# modem_tda.net
KiCad netlist of a schematic drawn in EAGLE
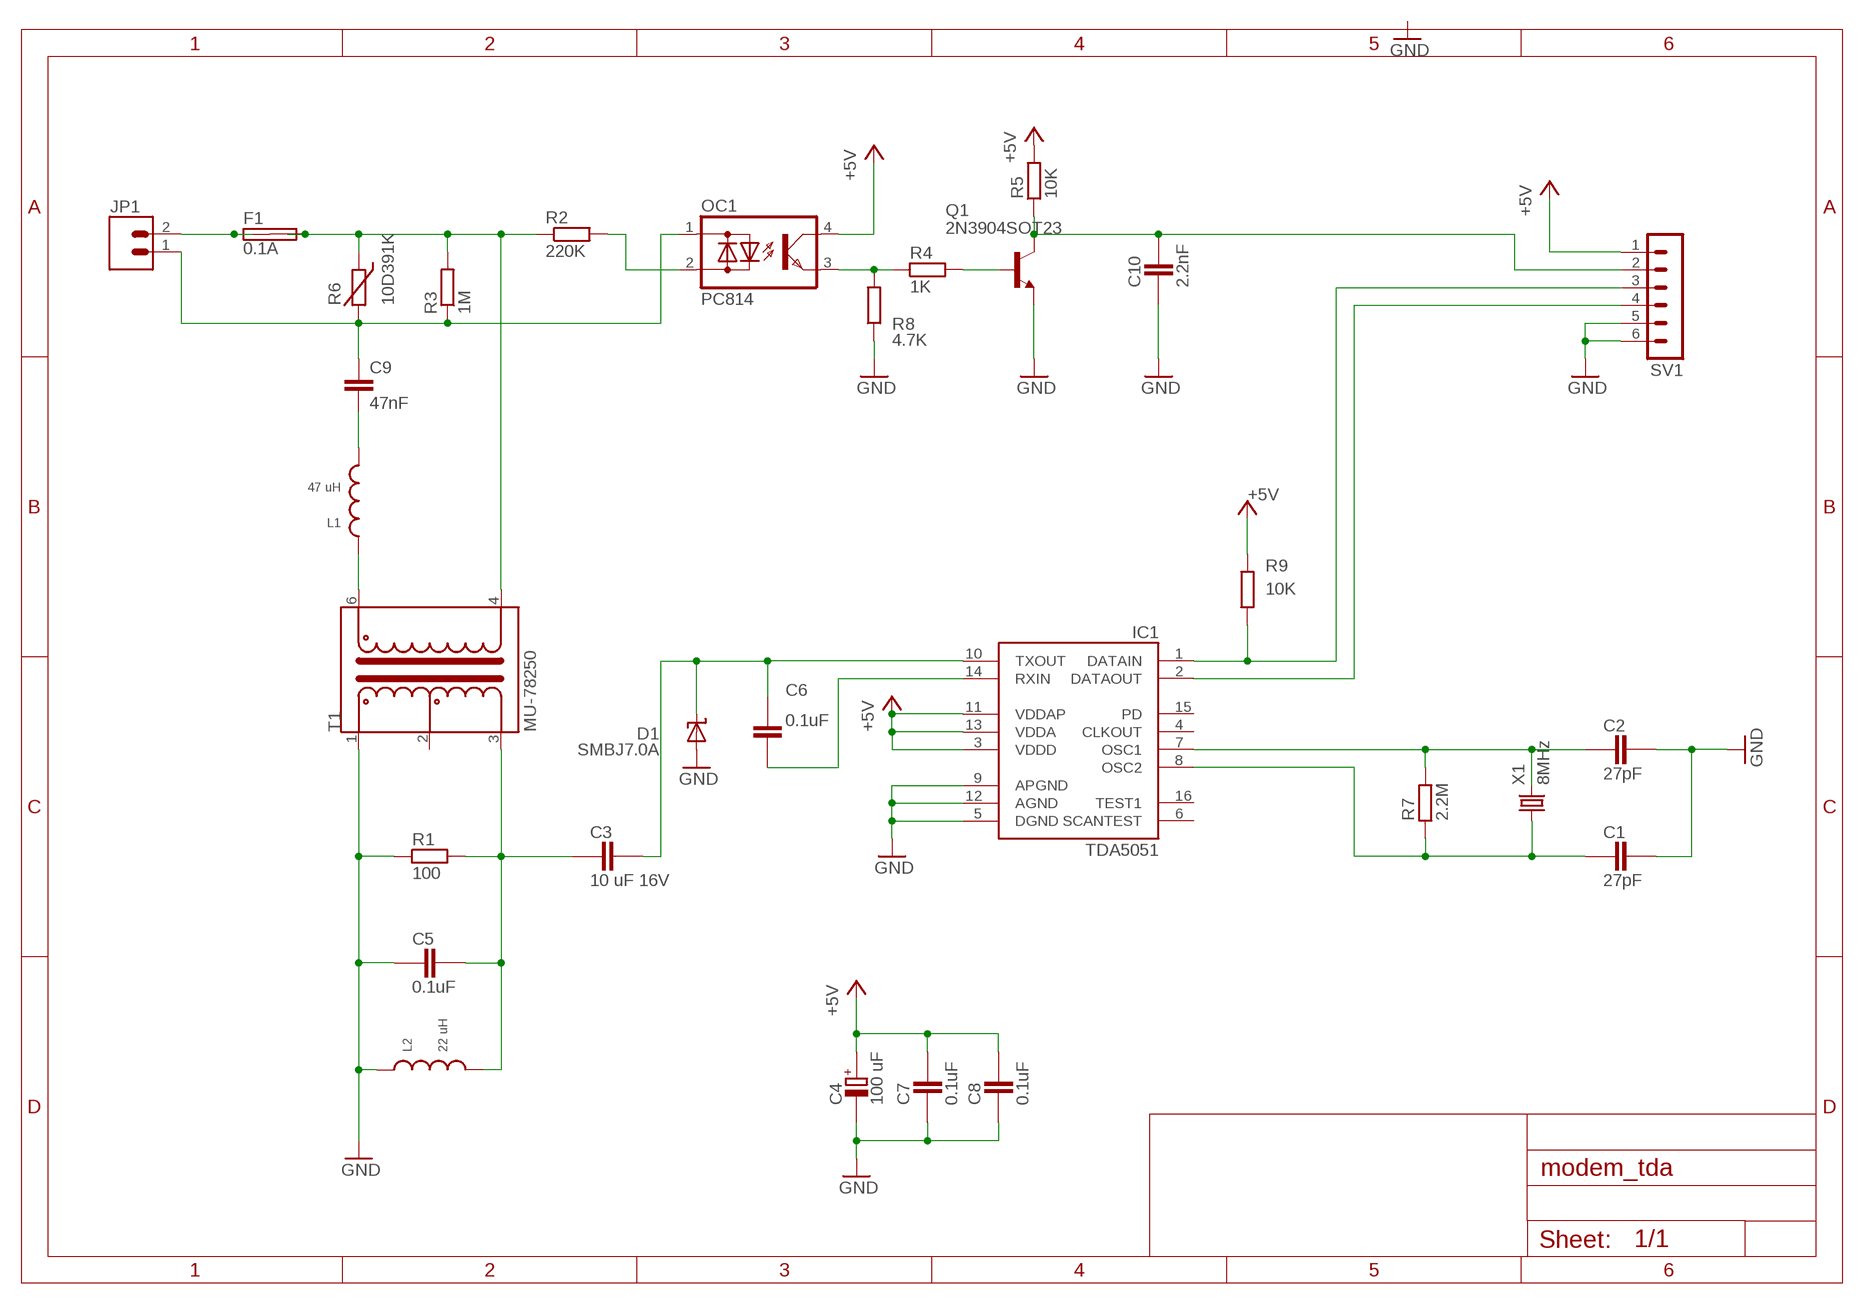
[diagram p0: schematic, sheet 1]

(export (version "E")
  (design (tool "Eeschema 10.0.6"))
  (components
    (comp (ref "C1")
      (value "27pF")
      (footprint "eagle-import:CAPC2012X145AN")
      (libsource (lib "eagle-import") (part "CAPACITOR_0805"))
    )
    (comp (ref "C2")
      (value "27pF")
      (footprint "eagle-import:CAPC2012X145AN")
      (libsource (lib "eagle-import") (part "CAPACITOR_0805"))
    )
    (comp (ref "C3")
      (value "10 uF 16V")
      (footprint "eagle-import:CAPC3215X168N")
      (libsource (lib "eagle-import") (part "CAPACITOR_1206"))
    )
    (comp (ref "C4")
      (value "100 uF")
      (footprint "eagle-import:CAPMP6032X150N")
      (libsource (lib "eagle-import") (part "POLARISED_U_CASE"))
    )
    (comp (ref "C5")
      (value "0.1uF")
      (footprint "eagle-import:CAPC2012X145AN")
      (libsource (lib "eagle-import") (part "CAPACITOR_0805"))
    )
    (comp (ref "C6")
      (value "0.1uF")
      (footprint "eagle-import:CAPC2012X145AN")
      (libsource (lib "eagle-import") (part "CAPACITOR_0805"))
    )
    (comp (ref "C7")
      (value "0.1uF")
      (footprint "eagle-import:CAPC2012X145AN")
      (libsource (lib "eagle-import") (part "CAPACITOR_0805"))
    )
    (comp (ref "C8")
      (value "0.1uF")
      (footprint "eagle-import:CAPC2012X145AN")
      (libsource (lib "eagle-import") (part "CAPACITOR_0805"))
    )
    (comp (ref "C9")
      (value "47nF")
      (footprint "eagle-import:XC10B6")
      (libsource (lib "eagle-import") (part "CXXC10B6"))
    )
    (comp (ref "C10")
      (value "2.2nF")
      (footprint "eagle-import:CAPC2012X145AN")
      (libsource (lib "eagle-import") (part "CAPACITOR_0805"))
    )
    (comp (ref "D1")
      (value "SMBJ7.0A")
      (footprint "eagle-import:SMBJ")
      (libsource (lib "eagle-import") (part "SUPPRESSOR-SMBJ"))
    )
    (comp (ref "F1")
      (value "0.1A")
      (footprint "eagle-import:SHK20L")
      (libsource (lib "eagle-import") (part "SHK20L"))
    )
    (comp (ref "IC1")
      (value "TDA5051")
      (footprint "eagle-import:SO16W")
      (libsource (lib "eagle-import") (part "TDA5051"))
    )
    (comp (ref "JP1")
      (value "BLUE_TERM")
      (footprint "eagle-import:BLUE_TERM")
      (libsource (lib "eagle-import") (part "BLUE_TERM"))
    )
    (comp (ref "L1")
      (value "47 uH")
      (footprint "eagle-import:CD43")
      (libsource (lib "eagle-import") (part "L-US"))
    )
    (comp (ref "L2")
      (value "22 uH")
      (footprint "eagle-import:CD43")
      (libsource (lib "eagle-import") (part "L-US"))
    )
    (comp (ref "OC1")
      (value "PC814")
      (footprint "eagle-import:DIL04")
      (libsource (lib "eagle-import") (part "PC814"))
    )
    (comp (ref "Q1")
      (value "2N3904SOT23")
      (footprint "eagle-import:SOT23-BEC")
      (libsource (lib "eagle-import") (part "2N3904SOT23"))
    )
    (comp (ref "R1")
      (value "100")
      (footprint "eagle-import:RESC2012X70N")
      (libsource (lib "eagle-import") (part "RESISTOR_0805"))
    )
    (comp (ref "R2")
      (value "220K")
      (footprint "eagle-import:0309_12")
      (libsource (lib "eagle-import") (part "R-EU_0309/12"))
    )
    (comp (ref "R3")
      (value "1M")
      (footprint "eagle-import:0207_10")
      (libsource (lib "eagle-import") (part "R-EU_0207/10"))
    )
    (comp (ref "R4")
      (value "1K")
      (footprint "eagle-import:RESC2012X70N")
      (libsource (lib "eagle-import") (part "RESISTOR_0805"))
    )
    (comp (ref "R5")
      (value "10K")
      (footprint "eagle-import:RESC2012X70N")
      (libsource (lib "eagle-import") (part "RESISTOR_0805"))
    )
    (comp (ref "R6")
      (value "10D391K")
      (footprint "eagle-import:MOV-10D")
      (libsource (lib "eagle-import") (part "VARISTOR"))
    )
    (comp (ref "R7")
      (value "2.2M")
      (footprint "eagle-import:RESC2012X70N")
      (libsource (lib "eagle-import") (part "RESISTOR_0805"))
    )
    (comp (ref "R8")
      (value "4.7K")
      (footprint "eagle-import:RESC2012X70N")
      (libsource (lib "eagle-import") (part "RESISTOR_0805"))
    )
    (comp (ref "R9")
      (value "10K")
      (footprint "eagle-import:RESC2012X70N")
      (libsource (lib "eagle-import") (part "RESISTOR_0805"))
    )
    (comp (ref "SV1")
      (value "MA06-1")
      (footprint "eagle-import:MA06-1")
      (libsource (lib "eagle-import") (part "MA06-1"))
    )
    (comp (ref "T1")
      (value "MU-78250")
      (footprint "eagle-import:6-PIN-DIL")
      (libsource (lib "eagle-import") (part "MU-78250"))
    )
    (comp (ref "X1")
      (value "8MHz")
      (footprint "eagle-import:HC49_S")
      (libsource (lib "eagle-import") (part "CRYSTALHC49S"))
    )
  )
  (nets
    (net (code "1") (name "+5V") (class "Default")
      (node (ref "C4") (pin "+") (pinfunction "+_+") (pintype "passive"))
      (node (ref "C7") (pin "2") (pinfunction "2_2") (pintype "passive"))
      (node (ref "C8") (pin "2") (pinfunction "2_2") (pintype "passive"))
      (node (ref "IC1") (pin "11") (pinfunction "VDDAP_11") (pintype "power_in"))
      (node (ref "IC1") (pin "13") (pinfunction "VDDA_13") (pintype "power_in"))
      (node (ref "IC1") (pin "3") (pinfunction "VDDD_3") (pintype "power_in"))
      (node (ref "OC1") (pin "4") (pinfunction "C_4") (pintype "passive"))
      (node (ref "R5") (pin "2") (pinfunction "2_2") (pintype "passive"))
      (node (ref "R9") (pin "2") (pinfunction "2_2") (pintype "passive"))
      (node (ref "SV1") (pin "1") (pinfunction "1_1") (pintype "passive"))
    )
    (net (code "2") (name "GND") (class "Default")
      (node (ref "C1") (pin "2") (pinfunction "2_2") (pintype "passive"))
      (node (ref "C10") (pin "1") (pinfunction "1_1") (pintype "passive"))
      (node (ref "C2") (pin "2") (pinfunction "2_2") (pintype "passive"))
      (node (ref "C4") (pin "-") (pinfunction "-_-") (pintype "passive"))
      (node (ref "C5") (pin "1") (pinfunction "1_1") (pintype "passive"))
      (node (ref "C7") (pin "1") (pinfunction "1_1") (pintype "passive"))
      (node (ref "C8") (pin "1") (pinfunction "1_1") (pintype "passive"))
      (node (ref "D1") (pin "A") (pinfunction "A_A") (pintype "passive"))
      (node (ref "IC1") (pin "12") (pinfunction "AGND_12") (pintype "power_in"))
      (node (ref "IC1") (pin "5") (pinfunction "DGND_5") (pintype "power_in"))
      (node (ref "IC1") (pin "9") (pinfunction "APGND_9") (pintype "bidirectional"))
      (node (ref "L2") (pin "1") (pinfunction "1_1") (pintype "bidirectional"))
      (node (ref "Q1") (pin "E") (pinfunction "E_E") (pintype "passive"))
      (node (ref "R1") (pin "1") (pinfunction "1_1") (pintype "passive"))
      (node (ref "R8") (pin "1") (pinfunction "1_1") (pintype "passive"))
      (node (ref "SV1") (pin "5") (pinfunction "5_5") (pintype "passive"))
      (node (ref "SV1") (pin "6") (pinfunction "6_6") (pintype "passive"))
      (node (ref "T1") (pin "1") (pinfunction "1_1") (pintype "bidirectional"))
    )
    (net (code "3") (name "Net-(C3-Pad1)") (class "Default")
      (node (ref "C3") (pin "1") (pinfunction "1_1") (pintype "passive"))
      (node (ref "C5") (pin "2") (pinfunction "2_2") (pintype "passive"))
      (node (ref "L2") (pin "2") (pinfunction "2_2") (pintype "bidirectional"))
      (node (ref "R1") (pin "2") (pinfunction "2_2") (pintype "passive"))
      (node (ref "T1") (pin "3") (pinfunction "3_3") (pintype "bidirectional"))
    )
    (net (code "4") (name "Net-(C9-Pad2)") (class "Default")
      (node (ref "C9") (pin "2") (pinfunction "2_2") (pintype "passive"))
      (node (ref "L1") (pin "2") (pinfunction "2_2") (pintype "bidirectional"))
    )
    (net (code "5") (name "Net-(C10-Pad2)") (class "Default")
      (node (ref "C10") (pin "2") (pinfunction "2_2") (pintype "passive"))
      (node (ref "Q1") (pin "C") (pinfunction "C_C") (pintype "passive"))
      (node (ref "R5") (pin "1") (pinfunction "1_1") (pintype "passive"))
      (node (ref "SV1") (pin "2") (pinfunction "2_2") (pintype "passive"))
    )
    (net (code "6") (name "Net-(F1-Pad1A)") (class "Default")
      (node (ref "F1") (pin "1A") (pinfunction "1A_1A") (pintype "passive"))
      (node (ref "F1") (pin "1B") (pinfunction "1B_1B") (pintype "passive"))
      (node (ref "JP1") (pin "2") (pinfunction "2_2") (pintype "passive"))
    )
    (net (code "7") (name "Net-(F1-Pad2A)") (class "Default")
      (node (ref "F1") (pin "2A") (pinfunction "2A_2A") (pintype "passive"))
      (node (ref "F1") (pin "2B") (pinfunction "2B_2B") (pintype "passive"))
      (node (ref "R2") (pin "1") (pinfunction "1_1") (pintype "passive"))
      (node (ref "R3") (pin "2") (pinfunction "2_2") (pintype "passive"))
      (node (ref "R6") (pin "2") (pinfunction "2_2") (pintype "bidirectional"))
      (node (ref "T1") (pin "4") (pinfunction "4_4") (pintype "bidirectional"))
    )
    (net (code "8") (name "Net-(IC1-DATAIN)") (class "Default")
      (node (ref "IC1") (pin "1") (pinfunction "DATAIN_1") (pintype "input"))
      (node (ref "R9") (pin "1") (pinfunction "1_1") (pintype "passive"))
      (node (ref "SV1") (pin "3") (pinfunction "3_3") (pintype "passive"))
    )
    (net (code "9") (name "Net-(IC1-DATAOUT)") (class "Default")
      (node (ref "IC1") (pin "2") (pinfunction "DATAOUT_2") (pintype "output"))
      (node (ref "SV1") (pin "4") (pinfunction "4_4") (pintype "passive"))
    )
    (net (code "10") (name "Net-(IC1-OSC1)") (class "Default")
      (node (ref "C2") (pin "1") (pinfunction "1_1") (pintype "passive"))
      (node (ref "IC1") (pin "7") (pinfunction "OSC1_7") (pintype "bidirectional"))
      (node (ref "R7") (pin "2") (pinfunction "2_2") (pintype "passive"))
      (node (ref "X1") (pin "2") (pinfunction "2_2") (pintype "passive"))
    )
    (net (code "11") (name "Net-(IC1-OSC2)") (class "Default")
      (node (ref "C1") (pin "1") (pinfunction "1_1") (pintype "passive"))
      (node (ref "IC1") (pin "8") (pinfunction "OSC2_8") (pintype "bidirectional"))
      (node (ref "R7") (pin "1") (pinfunction "1_1") (pintype "passive"))
      (node (ref "X1") (pin "1") (pinfunction "1_1") (pintype "passive"))
    )
    (net (code "12") (name "Net-(IC1-RXIN)") (class "Default")
      (node (ref "C6") (pin "1") (pinfunction "1_1") (pintype "passive"))
      (node (ref "IC1") (pin "14") (pinfunction "RXIN_14") (pintype "input"))
    )
    (net (code "13") (name "Net-(IC1-TXOUT)") (class "Default")
      (node (ref "C3") (pin "2") (pinfunction "2_2") (pintype "passive"))
      (node (ref "C6") (pin "2") (pinfunction "2_2") (pintype "passive"))
      (node (ref "D1") (pin "C") (pinfunction "C_C") (pintype "passive"))
      (node (ref "IC1") (pin "10") (pinfunction "TXOUT_10") (pintype "output"))
    )
    (net (code "14") (name "Net-(L1-Pad1)") (class "Default")
      (node (ref "L1") (pin "1") (pinfunction "1_1") (pintype "bidirectional"))
      (node (ref "T1") (pin "6") (pinfunction "6_6") (pintype "bidirectional"))
    )
    (net (code "15") (name "Net-(OC1-AC1)") (class "Default")
      (node (ref "C9") (pin "1") (pinfunction "1_1") (pintype "passive"))
      (node (ref "JP1") (pin "1") (pinfunction "1_1") (pintype "passive"))
      (node (ref "OC1") (pin "1") (pinfunction "AC1_1") (pintype "passive"))
      (node (ref "R3") (pin "1") (pinfunction "1_1") (pintype "passive"))
      (node (ref "R6") (pin "1") (pinfunction "1_1") (pintype "bidirectional"))
    )
    (net (code "16") (name "Net-(OC1-AC2)") (class "Default")
      (node (ref "OC1") (pin "2") (pinfunction "AC2_2") (pintype "passive"))
      (node (ref "R2") (pin "2") (pinfunction "2_2") (pintype "passive"))
    )
    (net (code "17") (name "Net-(OC1-E)") (class "Default")
      (node (ref "OC1") (pin "3") (pinfunction "E_3") (pintype "passive"))
      (node (ref "R4") (pin "1") (pinfunction "1_1") (pintype "passive"))
      (node (ref "R8") (pin "2") (pinfunction "2_2") (pintype "passive"))
    )
    (net (code "18") (name "Net-(Q1-PadB)") (class "Default")
      (node (ref "Q1") (pin "B") (pinfunction "B_B") (pintype "passive"))
      (node (ref "R4") (pin "2") (pinfunction "2_2") (pintype "passive"))
    )
    (net (code "19") (name "unconnected-(IC1-CLKOUT-Pad4)") (class "Default")
      (node (ref "IC1") (pin "4") (pinfunction "CLKOUT_4") (pintype "output"))
    )
    (net (code "20") (name "unconnected-(IC1-PD-Pad15)") (class "Default")
      (node (ref "IC1") (pin "15") (pinfunction "PD_15") (pintype "input"))
    )
    (net (code "21") (name "unconnected-(IC1-SCANTEST-Pad6)") (class "Default")
      (node (ref "IC1") (pin "6") (pinfunction "SCANTEST_6") (pintype "bidirectional"))
    )
    (net (code "22") (name "unconnected-(IC1-TEST1-Pad16)") (class "Default")
      (node (ref "IC1") (pin "16") (pinfunction "TEST1_16") (pintype "bidirectional"))
    )
    (net (code "23") (name "unconnected-(T1-Pad2)") (class "Default")
      (node (ref "T1") (pin "2") (pinfunction "2_2") (pintype "bidirectional"))
    )
  )
)
